# fob-o-matic.net
KiCad netlist of a schematic drawn in EAGLE
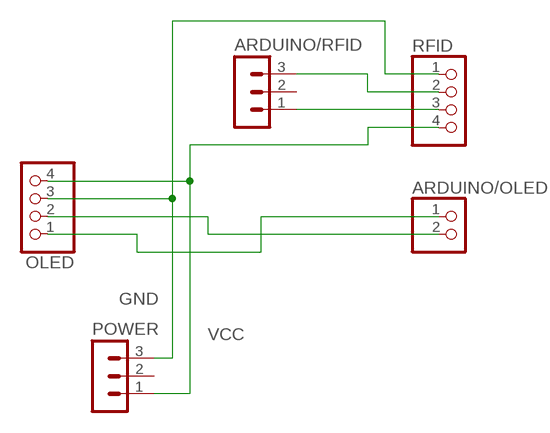
[diagram p0: schematic, sheet 1]

(export (version "E")
  (design (tool "Eeschema 10.0.6"))
  (components
    (comp (ref "ARDUINO/OLED")
      (value "PINHD-1X2")
      (footprint "eagle-import:1X02")
      (libsource (lib "eagle-import") (part "PINHD-1X2"))
    )
    (comp (ref "ARDUINO/RFID")
      (value "MA03-1")
      (footprint "eagle-import:MA03-1")
      (libsource (lib "eagle-import") (part "MA03-1"))
    )
    (comp (ref "OLED")
      (value "PINHD-1X4/90")
      (footprint "eagle-import:1X04_90")
      (libsource (lib "eagle-import") (part "PINHD-1X4/90"))
    )
    (comp (ref "POWER")
      (value "MA03-1")
      (footprint "eagle-import:MA03-1")
      (libsource (lib "eagle-import") (part "MA03-1"))
    )
    (comp (ref "RFID")
      (value "PINHD-1X4/90")
      (footprint "eagle-import:1X04_90")
      (libsource (lib "eagle-import") (part "PINHD-1X4/90"))
    )
  )
  (nets
    (net (code "1") (name "/GND") (class "Default")
      (node (ref "OLED") (pin "3") (pinfunction "3_3") (pintype "passive"))
      (node (ref "POWER") (pin "3") (pinfunction "3_3") (pintype "passive"))
      (node (ref "RFID") (pin "1") (pinfunction "1_1") (pintype "passive"))
    )
    (net (code "2") (name "/VCC") (class "Default")
      (node (ref "OLED") (pin "4") (pinfunction "4_4") (pintype "passive"))
      (node (ref "POWER") (pin "1") (pinfunction "1_1") (pintype "passive"))
      (node (ref "RFID") (pin "4") (pinfunction "4_4") (pintype "passive"))
    )
    (net (code "3") (name "Net-(ARDUINO/OLED-Pad1)") (class "Default")
      (node (ref "ARDUINO/OLED") (pin "1") (pinfunction "1_1") (pintype "passive"))
      (node (ref "OLED") (pin "1") (pinfunction "1_1") (pintype "passive"))
    )
    (net (code "4") (name "Net-(ARDUINO/OLED-Pad2)") (class "Default")
      (node (ref "ARDUINO/OLED") (pin "2") (pinfunction "2_2") (pintype "passive"))
      (node (ref "OLED") (pin "2") (pinfunction "2_2") (pintype "passive"))
    )
    (net (code "5") (name "Net-(ARDUINO/RFID-Pad1)") (class "Default")
      (node (ref "ARDUINO/RFID") (pin "1") (pinfunction "1_1") (pintype "passive"))
      (node (ref "RFID") (pin "3") (pinfunction "3_3") (pintype "passive"))
    )
    (net (code "6") (name "Net-(ARDUINO/RFID-Pad3)") (class "Default")
      (node (ref "ARDUINO/RFID") (pin "3") (pinfunction "3_3") (pintype "passive"))
      (node (ref "RFID") (pin "2") (pinfunction "2_2") (pintype "passive"))
    )
    (net (code "7") (name "unconnected-(ARDUINO/RFID-Pad2)") (class "Default")
      (node (ref "ARDUINO/RFID") (pin "2") (pinfunction "2_2") (pintype "passive"))
    )
    (net (code "8") (name "unconnected-(POWER-Pad2)") (class "Default")
      (node (ref "POWER") (pin "2") (pinfunction "2_2") (pintype "passive"))
    )
  )
)
